# PowerManagement.net
KiCad netlist of a schematic drawn in Altium Designer
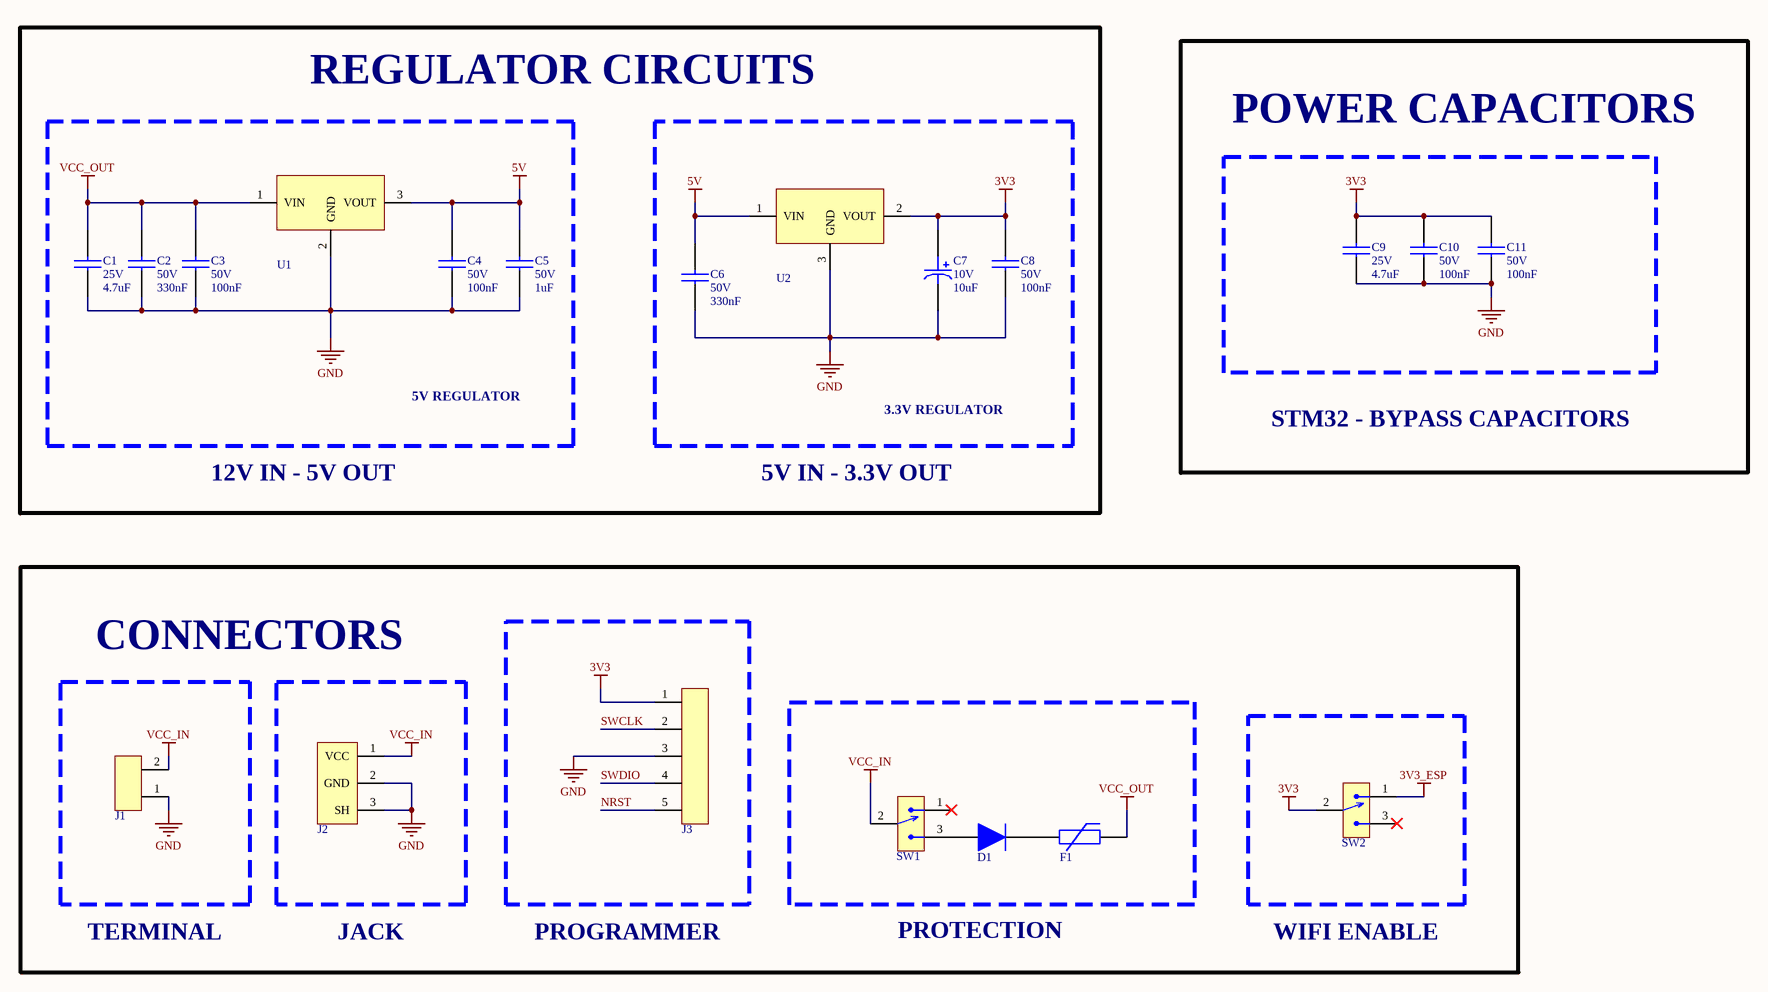
[diagram p0: PowerManagement.SchDoc]

(export (version "E")
  (design (tool "Eeschema 10.0.6"))
  (components
    (comp (ref "C1")
      (value "CL21A475KAQNNNE")
      (footprint "CAP_0805")
      (description "CAP CER 4.7uF %10 0805")
      (fields
        (field (name "MANUFACTURER") "Samsung")
        (field (name "TOLERANCE") "10%")
        (field (name "VOLTAGE RATING") "25V")
        (field (name "CAPACITANCE") "4.7uF")
        (field (name "DESIGNEDBY") "Aslı Kurt")
      )
      (libsource (lib "MyLibrary") (part "CAP CER 4.7uF 0805"))
    )
    (comp (ref "C2")
      (value "CGA3E3X7R1H334K080AB")
      (footprint "CAP_0603")
      (description "Multilayer Ceramic Capacitor, 0.33 uF, 50 V, ± 10%, X7R, 0603 [1608 Metric]")
      (fields
        (field (name "MANUFACTURER") "TDK")
        (field (name "TOLERANCE") "10%")
        (field (name "VOLTAGE RATING (DC)") "50V")
        (field (name "CAPACITANCE") "330nF")
        (field (name "DESIGNEDBY") "Aslı Kurt")
      )
      (libsource (lib "MyLibrary") (part "CAP CER 330nF 0603"))
    )
    (comp (ref "C3")
      (value "C0603C104K5RACTU")
      (footprint "CAP_0603")
      (description "CAP CER 100nF %10 0603 SMD")
      (fields
        (field (name "MANUFACTURER") "KEMET")
        (field (name "TOLERANCE") "10%")
        (field (name "VOLTAGE RATING (DC)") "50V")
        (field (name "CAPACITANCE") "100nF")
        (field (name "DESIGNEDBY") "Aslı Kurt")
      )
      (libsource (lib "MyLibrary") (part "CAP CER 100nF 0603"))
    )
    (comp (ref "C4")
      (value "C0603C104K5RACTU")
      (footprint "CAP_0603")
      (description "CAP CER 100nF %10 0603 SMD")
      (fields
        (field (name "MANUFACTURER") "KEMET")
        (field (name "TOLERANCE") "10%")
        (field (name "VOLTAGE RATING (DC)") "50V")
        (field (name "CAPACITANCE") "100nF")
        (field (name "DESIGNEDBY") "Aslı Kurt")
      )
      (libsource (lib "MyLibrary") (part "CAP CER 100nF 0603"))
    )
    (comp (ref "C5")
      (value "CL21B105KBFNNNE")
      (footprint "CAP_0805")
      (description "CAP CER 1uF %10 0805")
      (fields
        (field (name "MANUFACTURER") "Samsung")
        (field (name "TOLERANCE") "10%")
        (field (name "VOLTAGE RATING") "50V")
        (field (name "CAPACITANCE") "1uF")
        (field (name "DESIGNEDBY") "Aslı Kurt")
      )
      (libsource (lib "MyLibrary") (part "CAP CER 1uF 0805"))
    )
    (comp (ref "C6")
      (value "CGA3E3X7R1H334K080AB")
      (footprint "CAP_0603")
      (description "Multilayer Ceramic Capacitor, 0.33 uF, 50 V, ± 10%, X7R, 0603 [1608 Metric]")
      (fields
        (field (name "MANUFACTURER") "TDK")
        (field (name "TOLERANCE") "10%")
        (field (name "VOLTAGE RATING (DC)") "50V")
        (field (name "CAPACITANCE") "330nF")
        (field (name "DESIGNEDBY") "Aslı Kurt")
      )
      (libsource (lib "MyLibrary") (part "CAP CER 330nF 0603"))
    )
    (comp (ref "C7")
      (value "T491A106K010AT")
      (footprint "CAP_1206_TANT")
      (description "Cap Tant Solid 10uF 10V A CASE 10% (3.2 X 1.6 X 1.6mm) SMD 3216-18 4 Ohm 125 C T/R")
      (fields
        (field (name "MANUFACTURER") "KEMET")
        (field (name "TOLERANCE") "10%")
        (field (name "VOLTAGE RATING") "10V")
        (field (name "CAPACITANCE") "10uF")
        (field (name "DESIGNEDBY") "Aslı Kurt")
      )
      (libsource (lib "MyLibrary") (part "CAP TANT 10uF 1206"))
    )
    (comp (ref "C8")
      (value "C0603C104K5RACTU")
      (footprint "CAP_0603")
      (description "CAP CER 100nF %10 0603 SMD")
      (fields
        (field (name "MANUFACTURER") "KEMET")
        (field (name "TOLERANCE") "10%")
        (field (name "VOLTAGE RATING (DC)") "50V")
        (field (name "CAPACITANCE") "100nF")
        (field (name "DESIGNEDBY") "Aslı Kurt")
      )
      (libsource (lib "MyLibrary") (part "CAP CER 100nF 0603"))
    )
    (comp (ref "C9")
      (value "CL21A475KAQNNNE")
      (footprint "CAP_0805")
      (description "CAP CER 4.7uF %10 0805")
      (fields
        (field (name "MANUFACTURER") "Samsung")
        (field (name "TOLERANCE") "10%")
        (field (name "VOLTAGE RATING") "25V")
        (field (name "CAPACITANCE") "4.7uF")
        (field (name "DESIGNEDBY") "Aslı Kurt")
      )
      (libsource (lib "MyLibrary") (part "CAP CER 4.7uF 0805"))
    )
    (comp (ref "C10")
      (value "C0603C104K5RACTU")
      (footprint "CAP_0603")
      (description "CAP CER 100nF %10 0603 SMD")
      (fields
        (field (name "MANUFACTURER") "KEMET")
        (field (name "TOLERANCE") "10%")
        (field (name "VOLTAGE RATING (DC)") "50V")
        (field (name "CAPACITANCE") "100nF")
        (field (name "DESIGNEDBY") "Aslı Kurt")
      )
      (libsource (lib "MyLibrary") (part "CAP CER 100nF 0603"))
    )
    (comp (ref "C11")
      (value "C0603C104K5RACTU")
      (footprint "CAP_0603")
      (description "CAP CER 100nF %10 0603 SMD")
      (fields
        (field (name "MANUFACTURER") "KEMET")
        (field (name "TOLERANCE") "10%")
        (field (name "VOLTAGE RATING (DC)") "50V")
        (field (name "CAPACITANCE") "100nF")
        (field (name "DESIGNEDBY") "Aslı Kurt")
      )
      (libsource (lib "MyLibrary") (part "CAP CER 100nF 0603"))
    )
    (comp (ref "D1")
      (value "1N4148WS")
      (footprint "SOD323F")
      (description "Diode, Single, 75 V, 150 mA, 1 V, 4 ns")
      (fields
        (field (name "MANUFACTURER") "ON Semiconductor / Fairchild")
        (field (name "DESIGNEDBY") "Aslı Kurt")
      )
      (libsource (lib "MyLibrary") (part "1N4148WS"))
    )
    (comp (ref "F1")
      (value "PRG21BC1R0MM1RA")
      (footprint "FUSE_0805")
      (description "Thermistor PTC 1 Ohm 20% 2-Pin 0805 Surface Mount Solder Pad Embossed T/R")
      (fields (field (name "MANUFACTURER") "Murata") (field (name "DESIGNEDBY") "Aslı Kurt"))
      (libsource (lib "MyLibrary") (part "PRG21BC1R0MM1RA"))
    )
    (comp (ref "J1")
      (value "282836-2")
      (footprint "TERMINAL")
      (description "Connector, Terminal Block; Wire Receptacle; 2 Pos.; 16-30 AWG; 0.197 in. CL; Sid")
      (fields
        (field (name "MANUFACTURER") "TE Connectivity")
        (field (name "VOLTAGE") "300V")
        (field (name "DESIGNEDBY") "Aslı Kurt")
      )
      (libsource (lib "MyLibrary") (part "2x1 TERMINAL 5mm"))
    )
    (comp (ref "J2")
      (value "PJ-037AH-SMT-TR")
      (footprint "JACK")
      (description "DC Power Connectors Power Jacks")
      (fields (field (name "MANUFACTURER") "CUI") (field (name "DESIGNEDBY") "Aslı Kurt"))
      (libsource (lib "MyLibrary") (part "PJ-037AH-SMT-TR"))
    )
    (comp (ref "J3")
      (value "61300511121")
      (footprint "5x1 Male Header 2.54mm")
      (fields (field (name "DESIGNEDBY") "Aslı Kurt"))
      (libsource (lib "MyLibrary") (part "5x1 Male Header 2.54mm"))
    )
    (comp (ref "SW1")
      (value "EG1215AA")
      (footprint "EG1215AA")
      (description "Slide Switch, SPDT, 0.025A, 24V, SMD")
      (fields
        (field (name "MANUFACTURER") "E-Switch")
        (field (name "TOLERANCE") "4.95%")
        (field (name "DESIGNEDBY") "Aslı Kurt")
      )
      (libsource (lib "MyLibrary") (part "EG1215AA"))
    )
    (comp (ref "SW2")
      (value "EG1215AA")
      (footprint "EG1215AA")
      (description "Slide Switch, SPDT, 0.025A, 24V, SMD")
      (fields
        (field (name "MANUFACTURER") "E-Switch")
        (field (name "TOLERANCE") "4.95%")
        (field (name "DESIGNEDBY") "Aslı Kurt")
      )
      (libsource (lib "MyLibrary") (part "EG1215AA"))
    )
    (comp (ref "U1")
      (value "L7805CD2T-TR")
      (footprint "D2PAK-TO-263-3")
      (description "Standard Regulator Pos 5V 1.5A 3-Pin(2+Tab) D2PAK T/R / IC REG LDO 5V 1.5A D2PAK")
      (fields (field (name "MANUFACTURER") "STMicroelectronics") (field (name "DESIGNEDBY") "Aslı Kurt"))
      (libsource (lib "MyLibrary") (part "L7805CD2T-TR"))
    )
    (comp (ref "U2")
      (value "LD29150DT33R")
      (footprint "DPAK-TO252")
      (description "LD29150 Series 3.3 V 1.5 A Fixed Output SMT LDO Voltage Regulator - TO-252")
      (fields (field (name "MANUFACTURER") "STMicroelectronics") (field (name "DESIGNEDBY") "Aslı Kurt"))
      (libsource (lib "MyLibrary") (part "LD29150DT33R"))
    )
  )
  (nets
    (net (code "1") (name "/NRST") (class "Default")
      (node (ref "J3") (pin "5") (pinfunction "5_5") (pintype "passive"))
    )
    (net (code "2") (name "/SWCLK") (class "Default")
      (node (ref "J3") (pin "2") (pinfunction "2_2") (pintype "power_in"))
    )
    (net (code "3") (name "/SWDIO") (class "Default")
      (node (ref "J3") (pin "4") (pinfunction "4_4") (pintype "power_in"))
    )
    (net (code "4") (name "3V3") (class "Default")
      (node (ref "C10") (pin "2") (pinfunction "2_2") (pintype "passive"))
      (node (ref "C11") (pin "2") (pinfunction "2_2") (pintype "passive"))
      (node (ref "C7") (pin "1") (pinfunction "1_1") (pintype "passive"))
      (node (ref "C8") (pin "2") (pinfunction "2_2") (pintype "passive"))
      (node (ref "C9") (pin "2") (pinfunction "2_2") (pintype "passive"))
      (node (ref "J3") (pin "1") (pinfunction "1_1") (pintype "power_in"))
      (node (ref "SW2") (pin "2") (pinfunction "2_2") (pintype "passive"))
      (node (ref "U2") (pin "2") (pinfunction "VOUT_2") (pintype "passive"))
    )
    (net (code "5") (name "3V3_ESP") (class "Default")
      (node (ref "SW2") (pin "1") (pinfunction "1_1") (pintype "passive"))
    )
    (net (code "6") (name "5V") (class "Default")
      (node (ref "C4") (pin "2") (pinfunction "2_2") (pintype "passive"))
      (node (ref "C5") (pin "2") (pinfunction "2_2") (pintype "passive"))
      (node (ref "C6") (pin "2") (pinfunction "2_2") (pintype "passive"))
      (node (ref "U1") (pin "3") (pinfunction "VOUT_3") (pintype "passive"))
      (node (ref "U2") (pin "1") (pinfunction "VIN_1") (pintype "passive"))
    )
    (net (code "7") (name "GND") (class "Default")
      (node (ref "C1") (pin "1") (pinfunction "1_1") (pintype "passive"))
      (node (ref "C10") (pin "1") (pinfunction "1_1") (pintype "passive"))
      (node (ref "C11") (pin "1") (pinfunction "1_1") (pintype "passive"))
      (node (ref "C2") (pin "1") (pinfunction "1_1") (pintype "passive"))
      (node (ref "C3") (pin "1") (pinfunction "1_1") (pintype "passive"))
      (node (ref "C4") (pin "1") (pinfunction "1_1") (pintype "passive"))
      (node (ref "C5") (pin "1") (pinfunction "1_1") (pintype "passive"))
      (node (ref "C6") (pin "1") (pinfunction "1_1") (pintype "passive"))
      (node (ref "C7") (pin "2") (pinfunction "2_2") (pintype "passive"))
      (node (ref "C8") (pin "1") (pinfunction "1_1") (pintype "passive"))
      (node (ref "C9") (pin "1") (pinfunction "1_1") (pintype "passive"))
      (node (ref "J1") (pin "1") (pinfunction "1_1") (pintype "passive"))
      (node (ref "J2") (pin "2") (pinfunction "GND_2") (pintype "power_in"))
      (node (ref "J2") (pin "3") (pinfunction "SH_3") (pintype "power_in"))
      (node (ref "J3") (pin "3") (pinfunction "3_3") (pintype "power_in"))
      (node (ref "U1") (pin "2") (pinfunction "GND_2") (pintype "passive"))
      (node (ref "U2") (pin "3") (pinfunction "GND_3") (pintype "passive"))
    )
    (net (code "8") (name "Net-(D1-Pad1)") (class "Default")
      (node (ref "D1") (pin "1") (pinfunction "1_1") (pintype "power_in"))
      (node (ref "SW1") (pin "3") (pinfunction "3_3") (pintype "passive"))
    )
    (net (code "9") (name "Net-(D1-Pad2)") (class "Default")
      (node (ref "D1") (pin "2") (pinfunction "2_2") (pintype "power_in"))
      (node (ref "F1") (pin "2") (pinfunction "2_2") (pintype "passive"))
    )
    (net (code "10") (name "VCC_IN") (class "Default")
      (node (ref "J1") (pin "2") (pinfunction "2_2") (pintype "passive"))
      (node (ref "J2") (pin "1") (pinfunction "VCC_1") (pintype "power_in"))
      (node (ref "SW1") (pin "2") (pinfunction "2_2") (pintype "passive"))
    )
    (net (code "11") (name "VCC_OUT") (class "Default")
      (node (ref "C1") (pin "2") (pinfunction "2_2") (pintype "passive"))
      (node (ref "C2") (pin "2") (pinfunction "2_2") (pintype "passive"))
      (node (ref "C3") (pin "2") (pinfunction "2_2") (pintype "passive"))
      (node (ref "F1") (pin "1") (pinfunction "1_1") (pintype "passive"))
      (node (ref "U1") (pin "1") (pinfunction "VIN_1") (pintype "passive"))
    )
    (net (code "12") (name "unconnected-(SW1-Pad1)") (class "Default")
      (node (ref "SW1") (pin "1") (pinfunction "1_1") (pintype "passive+no_connect"))
    )
    (net (code "13") (name "unconnected-(SW2-Pad3)") (class "Default")
      (node (ref "SW2") (pin "3") (pinfunction "3_3") (pintype "passive+no_connect"))
    )
  )
)
